# PDU_breakout.net
KiCad netlist of a schematic drawn in EAGLE
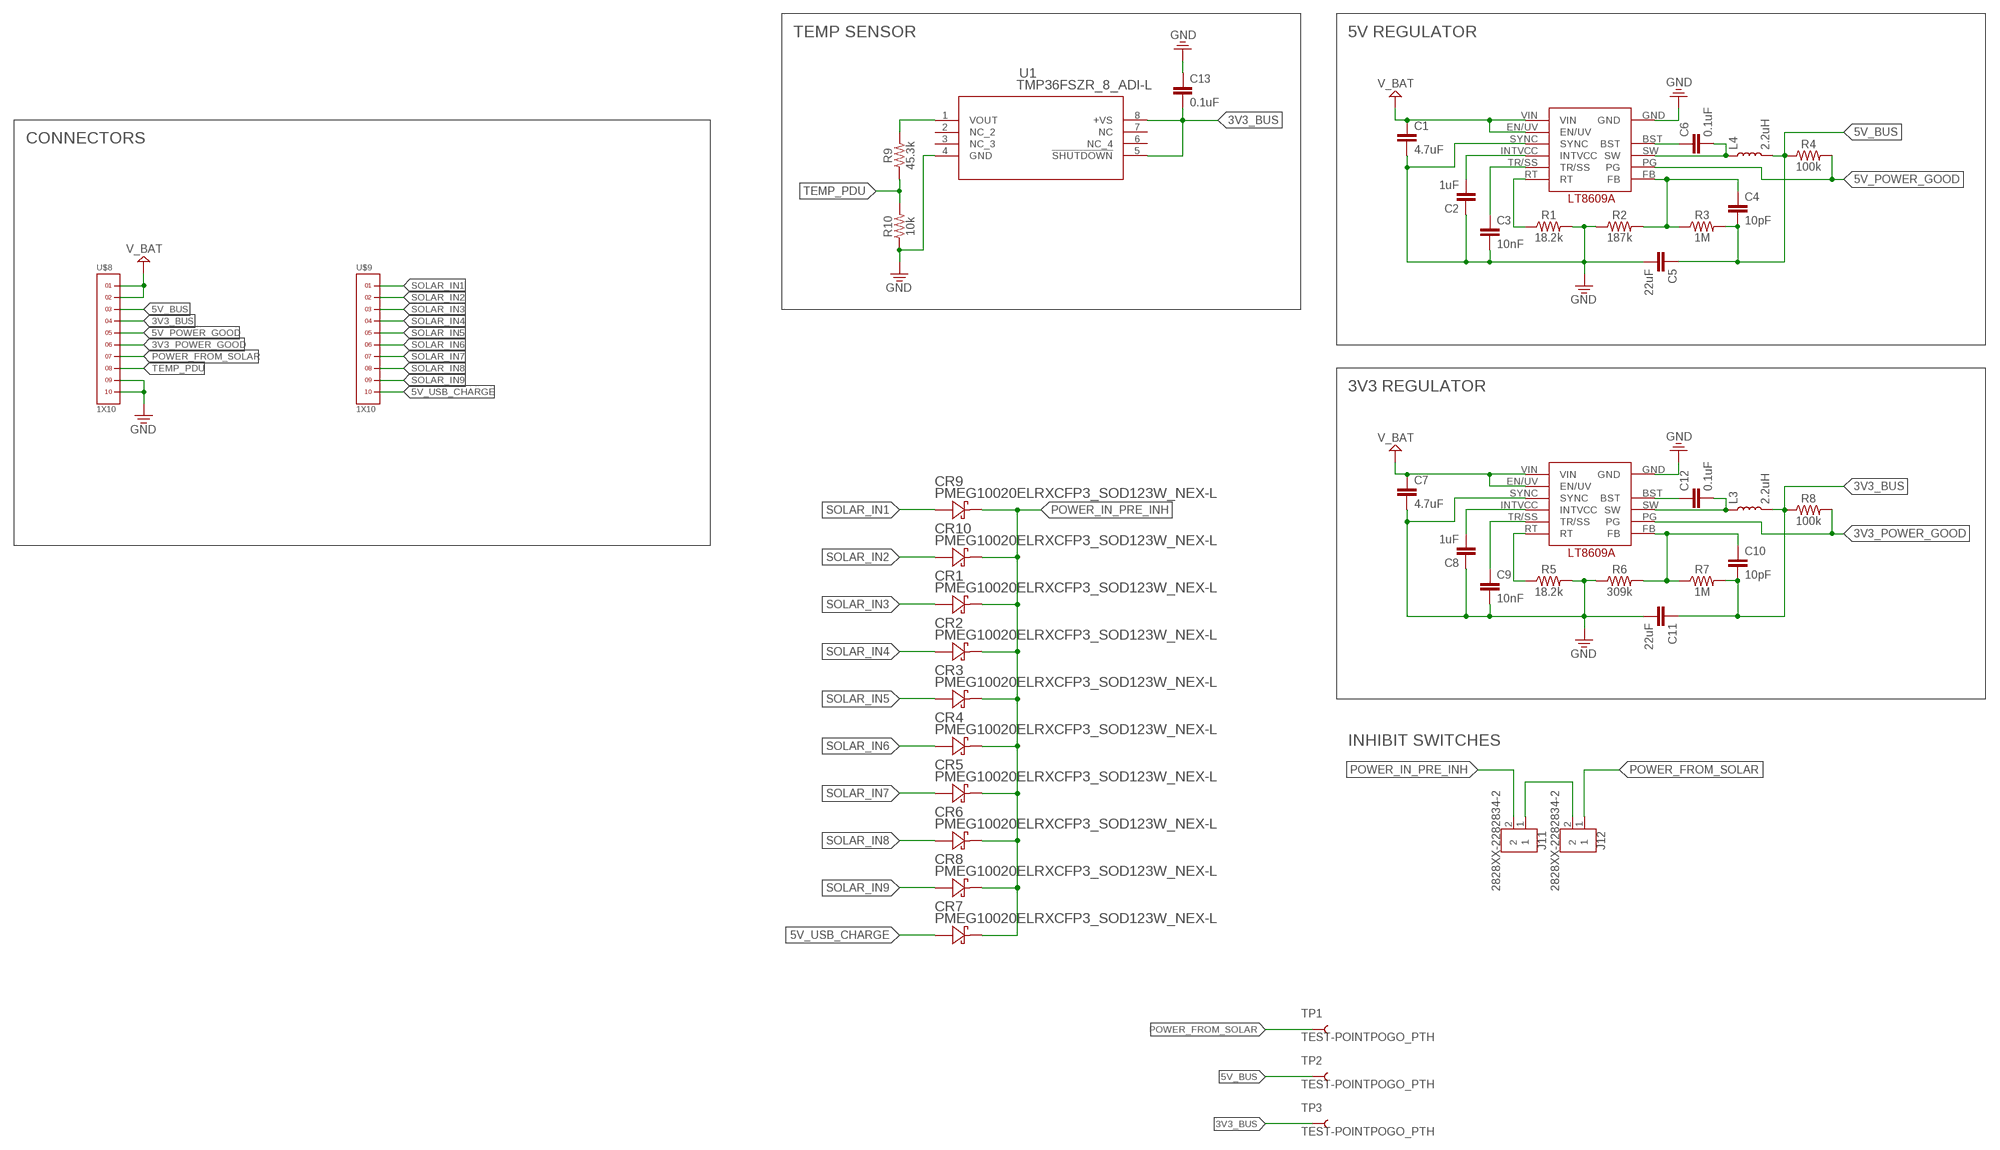
[diagram p0: schematic, sheet 1]

(export (version "E")
  (design (tool "Eeschema 10.0.6"))
  (components
    (comp (ref "C1")
      (value "4.7uF")
      (footprint "eagle-import:0805")
      (libsource (lib "eagle-import") (part "2.2UF-0805-25V-(+80/-20%)"))
    )
    (comp (ref "C2")
      (value "1uF")
      (footprint "eagle-import:0805")
      (libsource (lib "eagle-import") (part "2.2UF-0805-25V-(+80/-20%)"))
    )
    (comp (ref "C3")
      (value "10nF")
      (footprint "eagle-import:0805")
      (libsource (lib "eagle-import") (part "2.2UF-0805-25V-(+80/-20%)"))
    )
    (comp (ref "C4")
      (value "10pF")
      (footprint "eagle-import:0805")
      (libsource (lib "eagle-import") (part "2.2UF-0805-25V-(+80/-20%)"))
    )
    (comp (ref "C5")
      (value "22uF")
      (footprint "eagle-import:0805")
      (libsource (lib "eagle-import") (part "2.2UF-0805-25V-(+80/-20%)"))
    )
    (comp (ref "C6")
      (value "0.1uF")
      (footprint "eagle-import:0805")
      (libsource (lib "eagle-import") (part "2.2UF-0805-25V-(+80/-20%)"))
    )
    (comp (ref "C7")
      (value "4.7uF")
      (footprint "eagle-import:0805")
      (libsource (lib "eagle-import") (part "2.2UF-0805-25V-(+80/-20%)"))
    )
    (comp (ref "C8")
      (value "1uF")
      (footprint "eagle-import:0805")
      (libsource (lib "eagle-import") (part "2.2UF-0805-25V-(+80/-20%)"))
    )
    (comp (ref "C9")
      (value "10nF")
      (footprint "eagle-import:0805")
      (libsource (lib "eagle-import") (part "2.2UF-0805-25V-(+80/-20%)"))
    )
    (comp (ref "C10")
      (value "10pF")
      (footprint "eagle-import:0805")
      (libsource (lib "eagle-import") (part "2.2UF-0805-25V-(+80/-20%)"))
    )
    (comp (ref "C11")
      (value "22uF")
      (footprint "eagle-import:0805")
      (libsource (lib "eagle-import") (part "2.2UF-0805-25V-(+80/-20%)"))
    )
    (comp (ref "C12")
      (value "0.1uF")
      (footprint "eagle-import:0805")
      (libsource (lib "eagle-import") (part "2.2UF-0805-25V-(+80/-20%)"))
    )
    (comp (ref "C13")
      (value "0.1uF")
      (footprint "eagle-import:0805")
      (libsource (lib "eagle-import") (part "2.2UF-0805-25V-(+80/-20%)"))
    )
    (comp (ref "CR1")
      (value "PMEG10020ELRXCFP3_SOD123W_NEX-L")
      (footprint "eagle-import:CFP3_SOD123W_NEX-L")
      (fields
        (field (name "MANUFACTURER_PART_NUMBER") "PMEG10020ELRX")
        (field (name "COPYRIGHT") "Copyright (C) 2018 Accelerated Designs. All rights reserved")
      )
      (libsource (lib "eagle-import") (part "PMEG10020ELRXCFP3_SOD123W_NEX-L"))
    )
    (comp (ref "CR2")
      (value "PMEG10020ELRXCFP3_SOD123W_NEX-L")
      (footprint "eagle-import:CFP3_SOD123W_NEX-L")
      (fields
        (field (name "MANUFACTURER_PART_NUMBER") "PMEG10020ELRX")
        (field (name "COPYRIGHT") "Copyright (C) 2018 Accelerated Designs. All rights reserved")
      )
      (libsource (lib "eagle-import") (part "PMEG10020ELRXCFP3_SOD123W_NEX-L"))
    )
    (comp (ref "CR3")
      (value "PMEG10020ELRXCFP3_SOD123W_NEX-L")
      (footprint "eagle-import:CFP3_SOD123W_NEX-L")
      (fields
        (field (name "MANUFACTURER_PART_NUMBER") "PMEG10020ELRX")
        (field (name "COPYRIGHT") "Copyright (C) 2018 Accelerated Designs. All rights reserved")
      )
      (libsource (lib "eagle-import") (part "PMEG10020ELRXCFP3_SOD123W_NEX-L"))
    )
    (comp (ref "CR4")
      (value "PMEG10020ELRXCFP3_SOD123W_NEX-L")
      (footprint "eagle-import:CFP3_SOD123W_NEX-L")
      (fields
        (field (name "MANUFACTURER_PART_NUMBER") "PMEG10020ELRX")
        (field (name "COPYRIGHT") "Copyright (C) 2018 Accelerated Designs. All rights reserved")
      )
      (libsource (lib "eagle-import") (part "PMEG10020ELRXCFP3_SOD123W_NEX-L"))
    )
    (comp (ref "CR5")
      (value "PMEG10020ELRXCFP3_SOD123W_NEX-L")
      (footprint "eagle-import:CFP3_SOD123W_NEX-L")
      (fields
        (field (name "MANUFACTURER_PART_NUMBER") "PMEG10020ELRX")
        (field (name "COPYRIGHT") "Copyright (C) 2018 Accelerated Designs. All rights reserved")
      )
      (libsource (lib "eagle-import") (part "PMEG10020ELRXCFP3_SOD123W_NEX-L"))
    )
    (comp (ref "CR6")
      (value "PMEG10020ELRXCFP3_SOD123W_NEX-L")
      (footprint "eagle-import:CFP3_SOD123W_NEX-L")
      (fields
        (field (name "MANUFACTURER_PART_NUMBER") "PMEG10020ELRX")
        (field (name "COPYRIGHT") "Copyright (C) 2018 Accelerated Designs. All rights reserved")
      )
      (libsource (lib "eagle-import") (part "PMEG10020ELRXCFP3_SOD123W_NEX-L"))
    )
    (comp (ref "CR7")
      (value "PMEG10020ELRXCFP3_SOD123W_NEX-L")
      (footprint "eagle-import:CFP3_SOD123W_NEX-L")
      (fields
        (field (name "MANUFACTURER_PART_NUMBER") "PMEG10020ELRX")
        (field (name "COPYRIGHT") "Copyright (C) 2018 Accelerated Designs. All rights reserved")
      )
      (libsource (lib "eagle-import") (part "PMEG10020ELRXCFP3_SOD123W_NEX-L"))
    )
    (comp (ref "CR8")
      (value "PMEG10020ELRXCFP3_SOD123W_NEX-L")
      (footprint "eagle-import:CFP3_SOD123W_NEX-L")
      (fields
        (field (name "MANUFACTURER_PART_NUMBER") "PMEG10020ELRX")
        (field (name "COPYRIGHT") "Copyright (C) 2018 Accelerated Designs. All rights reserved")
      )
      (libsource (lib "eagle-import") (part "PMEG10020ELRXCFP3_SOD123W_NEX-L"))
    )
    (comp (ref "CR9")
      (value "PMEG10020ELRXCFP3_SOD123W_NEX-L")
      (footprint "eagle-import:CFP3_SOD123W_NEX-L")
      (fields
        (field (name "MANUFACTURER_PART_NUMBER") "PMEG10020ELRX")
        (field (name "COPYRIGHT") "Copyright (C) 2018 Accelerated Designs. All rights reserved")
      )
      (libsource (lib "eagle-import") (part "PMEG10020ELRXCFP3_SOD123W_NEX-L"))
    )
    (comp (ref "CR10")
      (value "PMEG10020ELRXCFP3_SOD123W_NEX-L")
      (footprint "eagle-import:CFP3_SOD123W_NEX-L")
      (fields
        (field (name "MANUFACTURER_PART_NUMBER") "PMEG10020ELRX")
        (field (name "COPYRIGHT") "Copyright (C) 2018 Accelerated Designs. All rights reserved")
      )
      (libsource (lib "eagle-import") (part "PMEG10020ELRXCFP3_SOD123W_NEX-L"))
    )
    (comp (ref "J11")
      (value "2828XX-2282834-2")
      (footprint "eagle-import:TERMBLK_254-2N")
      (fields (field (name "MANUFACTURER") "TE Connectivity AMP Connectors") (field (name "MPN") "282834-2 "))
      (libsource (lib "eagle-import") (part "2828XX-2282834-2"))
    )
    (comp (ref "J12")
      (value "2828XX-2282834-2")
      (footprint "eagle-import:TERMBLK_254-2N")
      (fields (field (name "MANUFACTURER") "TE Connectivity AMP Connectors") (field (name "MPN") "282834-2 "))
      (libsource (lib "eagle-import") (part "2828XX-2282834-2"))
    )
    (comp (ref "L3")
      (value "2.2uH")
      (footprint "eagle-import:XFL4020")
      (libsource (lib "eagle-import") (part "INDUCTOR-XFL40201.5UH"))
    )
    (comp (ref "L4")
      (value "2.2uH")
      (footprint "eagle-import:XFL4020")
      (libsource (lib "eagle-import") (part "INDUCTOR-XFL40201.5UH"))
    )
    (comp (ref "R1")
      (value "18.2k")
      (footprint "eagle-import:0805")
      (libsource (lib "eagle-import") (part "0.75OHM-0805-1/4W-1%"))
    )
    (comp (ref "R2")
      (value "187k")
      (footprint "eagle-import:0805")
      (libsource (lib "eagle-import") (part "0.75OHM-0805-1/4W-1%"))
    )
    (comp (ref "R3")
      (value "1M")
      (footprint "eagle-import:0805")
      (libsource (lib "eagle-import") (part "0.75OHM-0805-1/4W-1%"))
    )
    (comp (ref "R4")
      (value "100k")
      (footprint "eagle-import:0805")
      (libsource (lib "eagle-import") (part "0.75OHM-0805-1/4W-1%"))
    )
    (comp (ref "R5")
      (value "18.2k")
      (footprint "eagle-import:0805")
      (libsource (lib "eagle-import") (part "0.75OHM-0805-1/4W-1%"))
    )
    (comp (ref "R6")
      (value "309k")
      (footprint "eagle-import:0805")
      (libsource (lib "eagle-import") (part "0.75OHM-0805-1/4W-1%"))
    )
    (comp (ref "R7")
      (value "1M")
      (footprint "eagle-import:0805")
      (libsource (lib "eagle-import") (part "0.75OHM-0805-1/4W-1%"))
    )
    (comp (ref "R8")
      (value "100k")
      (footprint "eagle-import:0805")
      (libsource (lib "eagle-import") (part "0.75OHM-0805-1/4W-1%"))
    )
    (comp (ref "R9")
      (value "45.3k")
      (footprint "eagle-import:0805")
      (libsource (lib "eagle-import") (part "0.75OHM-0805-1/4W-1%"))
    )
    (comp (ref "R10")
      (value "10k")
      (footprint "eagle-import:0805")
      (libsource (lib "eagle-import") (part "0.75OHM-0805-1/4W-1%"))
    )
    (comp (ref "TP1")
      (value "TEST-POINTPOGO_PTH")
      (footprint "eagle-import:1X01_NO_SILK")
      (libsource (lib "eagle-import") (part "TEST-POINTPOGO_PTH"))
    )
    (comp (ref "TP2")
      (value "TEST-POINTPOGO_PTH")
      (footprint "eagle-import:1X01_NO_SILK")
      (libsource (lib "eagle-import") (part "TEST-POINTPOGO_PTH"))
    )
    (comp (ref "TP3")
      (value "TEST-POINTPOGO_PTH")
      (footprint "eagle-import:1X01_NO_SILK")
      (libsource (lib "eagle-import") (part "TEST-POINTPOGO_PTH"))
    )
    (comp (ref "U$1")
      (value "LT8609A-MSOP10")
      (footprint "eagle-import:LT8609A-MSE10")
      (libsource (lib "eagle-import") (part "LT8609A-MSOP10"))
    )
    (comp (ref "U$2")
      (value "LT8609A-MSOP10")
      (footprint "eagle-import:LT8609A-MSE10")
      (libsource (lib "eagle-import") (part "LT8609A-MSOP10"))
    )
    (comp (ref "U$8")
      (value "1X10")
      (footprint "eagle-import:1X10")
      (libsource (lib "eagle-import") (part "1X10"))
    )
    (comp (ref "U$9")
      (value "1X10")
      (footprint "eagle-import:1X10")
      (libsource (lib "eagle-import") (part "1X10"))
    )
    (comp (ref "U1")
      (value "TMP36FSZR_8_ADI-L")
      (footprint "eagle-import:R_8_ADI-L")
      (fields
        (field (name "MANUFACTURER_PART_NUMBER") "TMP36FSZ")
        (field (name "COPYRIGHT") "Copyright (C) 2021 Ultra Librarian. All rights reserved.")
      )
      (libsource (lib "eagle-import") (part "TMP36FSZR_8_ADI-L"))
    )
  )
  (nets
    (net (code "1") (name "3V3_BUS") (class "Default")
      (node (ref "C10") (pin "2") (pinfunction "2_2") (pintype "passive"))
      (node (ref "C11") (pin "1") (pinfunction "1_1") (pintype "passive"))
      (node (ref "C13") (pin "2") (pinfunction "2_2") (pintype "passive"))
      (node (ref "L3") (pin "P$2") (pinfunction "2_P$2") (pintype "passive"))
      (node (ref "R7") (pin "2") (pinfunction "2_2") (pintype "passive"))
      (node (ref "R8") (pin "1") (pinfunction "1_1") (pintype "passive"))
      (node (ref "TP3") (pin "1") (pinfunction "1_1") (pintype "bidirectional"))
      (node (ref "U$8") (pin "4") (pinfunction "4_4") (pintype "bidirectional"))
      (node (ref "U1") (pin "5") (pinfunction "~{SHUTDOWN}_5") (pintype "passive"))
      (node (ref "U1") (pin "8") (pinfunction "+VS_8") (pintype "power_in"))
    )
    (net (code "2") (name "3V3_POWER_GOOD") (class "Default")
      (node (ref "R8") (pin "2") (pinfunction "2_2") (pintype "passive"))
      (node (ref "U$2") (pin "PG") (pinfunction "PG_PG") (pintype "bidirectional"))
      (node (ref "U$8") (pin "6") (pinfunction "6_6") (pintype "bidirectional"))
    )
    (net (code "3") (name "5V_BUS") (class "Default")
      (node (ref "C4") (pin "2") (pinfunction "2_2") (pintype "passive"))
      (node (ref "C5") (pin "1") (pinfunction "1_1") (pintype "passive"))
      (node (ref "L4") (pin "P$2") (pinfunction "2_P$2") (pintype "passive"))
      (node (ref "R3") (pin "2") (pinfunction "2_2") (pintype "passive"))
      (node (ref "R4") (pin "1") (pinfunction "1_1") (pintype "passive"))
      (node (ref "TP2") (pin "1") (pinfunction "1_1") (pintype "bidirectional"))
      (node (ref "U$8") (pin "3") (pinfunction "3_3") (pintype "bidirectional"))
    )
    (net (code "4") (name "5V_POWER_GOOD") (class "Default")
      (node (ref "R4") (pin "2") (pinfunction "2_2") (pintype "passive"))
      (node (ref "U$1") (pin "PG") (pinfunction "PG_PG") (pintype "bidirectional"))
      (node (ref "U$8") (pin "5") (pinfunction "5_5") (pintype "bidirectional"))
    )
    (net (code "5") (name "5V_USB_CHARGE") (class "Default")
      (node (ref "CR7") (pin "2") (pinfunction "12_2") (pintype "passive"))
      (node (ref "U$9") (pin "10") (pinfunction "10_10") (pintype "bidirectional"))
    )
    (net (code "6") (name "GND") (class "Default")
      (node (ref "C1") (pin "2") (pinfunction "2_2") (pintype "passive"))
      (node (ref "C11") (pin "2") (pinfunction "2_2") (pintype "passive"))
      (node (ref "C13") (pin "1") (pinfunction "1_1") (pintype "passive"))
      (node (ref "C2") (pin "1") (pinfunction "1_1") (pintype "passive"))
      (node (ref "C3") (pin "2") (pinfunction "2_2") (pintype "passive"))
      (node (ref "C5") (pin "2") (pinfunction "2_2") (pintype "passive"))
      (node (ref "C7") (pin "2") (pinfunction "2_2") (pintype "passive"))
      (node (ref "C8") (pin "1") (pinfunction "1_1") (pintype "passive"))
      (node (ref "C9") (pin "2") (pinfunction "2_2") (pintype "passive"))
      (node (ref "R1") (pin "2") (pinfunction "2_2") (pintype "passive"))
      (node (ref "R10") (pin "1") (pinfunction "1_1") (pintype "passive"))
      (node (ref "R2") (pin "1") (pinfunction "1_1") (pintype "passive"))
      (node (ref "R5") (pin "2") (pinfunction "2_2") (pintype "passive"))
      (node (ref "R6") (pin "1") (pinfunction "1_1") (pintype "passive"))
      (node (ref "U$1") (pin "GND") (pinfunction "GND_GND") (pintype "bidirectional"))
      (node (ref "U$1") (pin "SYNC") (pinfunction "SYNC_SYNC") (pintype "bidirectional"))
      (node (ref "U$2") (pin "GND") (pinfunction "GND_GND") (pintype "bidirectional"))
      (node (ref "U$2") (pin "SYNC") (pinfunction "SYNC_SYNC") (pintype "bidirectional"))
      (node (ref "U$8") (pin "10") (pinfunction "10_10") (pintype "bidirectional"))
      (node (ref "U$8") (pin "9") (pinfunction "9_9") (pintype "bidirectional"))
      (node (ref "U1") (pin "4") (pinfunction "GND_4") (pintype "passive"))
    )
    (net (code "7") (name "Net-(C2-Pad2)") (class "Default")
      (node (ref "C2") (pin "2") (pinfunction "2_2") (pintype "passive"))
      (node (ref "U$1") (pin "INTVCC") (pinfunction "INTVCC_INTVCC") (pintype "bidirectional"))
    )
    (net (code "8") (name "Net-(C3-Pad1)") (class "Default")
      (node (ref "C3") (pin "1") (pinfunction "1_1") (pintype "passive"))
      (node (ref "U$1") (pin "TR/SS") (pinfunction "TR/SS_TR/SS") (pintype "bidirectional"))
    )
    (net (code "9") (name "Net-(C4-Pad1)") (class "Default")
      (node (ref "C4") (pin "1") (pinfunction "1_1") (pintype "passive"))
      (node (ref "R2") (pin "2") (pinfunction "2_2") (pintype "passive"))
      (node (ref "R3") (pin "1") (pinfunction "1_1") (pintype "passive"))
      (node (ref "U$1") (pin "FB") (pinfunction "FB_FB") (pintype "bidirectional"))
    )
    (net (code "10") (name "Net-(C6-Pad1)") (class "Default")
      (node (ref "C6") (pin "1") (pinfunction "1_1") (pintype "passive"))
      (node (ref "U$1") (pin "BST") (pinfunction "BST_BST") (pintype "bidirectional"))
    )
    (net (code "11") (name "Net-(C8-Pad2)") (class "Default")
      (node (ref "C8") (pin "2") (pinfunction "2_2") (pintype "passive"))
      (node (ref "U$2") (pin "INTVCC") (pinfunction "INTVCC_INTVCC") (pintype "bidirectional"))
    )
    (net (code "12") (name "Net-(C9-Pad1)") (class "Default")
      (node (ref "C9") (pin "1") (pinfunction "1_1") (pintype "passive"))
      (node (ref "U$2") (pin "TR/SS") (pinfunction "TR/SS_TR/SS") (pintype "bidirectional"))
    )
    (net (code "13") (name "Net-(C10-Pad1)") (class "Default")
      (node (ref "C10") (pin "1") (pinfunction "1_1") (pintype "passive"))
      (node (ref "R6") (pin "2") (pinfunction "2_2") (pintype "passive"))
      (node (ref "R7") (pin "1") (pinfunction "1_1") (pintype "passive"))
      (node (ref "U$2") (pin "FB") (pinfunction "FB_FB") (pintype "bidirectional"))
    )
    (net (code "14") (name "Net-(C12-Pad1)") (class "Default")
      (node (ref "C12") (pin "1") (pinfunction "1_1") (pintype "passive"))
      (node (ref "U$2") (pin "BST") (pinfunction "BST_BST") (pintype "bidirectional"))
    )
    (net (code "15") (name "Net-(J11-Pad1)") (class "Default")
      (node (ref "J11") (pin "1") (pinfunction "1_1") (pintype "bidirectional"))
      (node (ref "J12") (pin "2") (pinfunction "2_2") (pintype "bidirectional"))
    )
    (net (code "16") (name "Net-(L3-1)") (class "Default")
      (node (ref "C12") (pin "2") (pinfunction "2_2") (pintype "passive"))
      (node (ref "L3") (pin "P$1") (pinfunction "1_P$1") (pintype "passive"))
      (node (ref "U$2") (pin "SW") (pinfunction "SW_SW") (pintype "bidirectional"))
    )
    (net (code "17") (name "Net-(L4-1)") (class "Default")
      (node (ref "C6") (pin "2") (pinfunction "2_2") (pintype "passive"))
      (node (ref "L4") (pin "P$1") (pinfunction "1_P$1") (pintype "passive"))
      (node (ref "U$1") (pin "SW") (pinfunction "SW_SW") (pintype "bidirectional"))
    )
    (net (code "18") (name "Net-(R1-Pad1)") (class "Default")
      (node (ref "R1") (pin "1") (pinfunction "1_1") (pintype "passive"))
      (node (ref "U$1") (pin "RT") (pinfunction "RT_RT") (pintype "bidirectional"))
    )
    (net (code "19") (name "Net-(R5-Pad1)") (class "Default")
      (node (ref "R5") (pin "1") (pinfunction "1_1") (pintype "passive"))
      (node (ref "U$2") (pin "RT") (pinfunction "RT_RT") (pintype "bidirectional"))
    )
    (net (code "20") (name "Net-(U1-VOUT)") (class "Default")
      (node (ref "R9") (pin "2") (pinfunction "2_2") (pintype "passive"))
      (node (ref "U1") (pin "1") (pinfunction "VOUT_1") (pintype "output"))
    )
    (net (code "21") (name "POWER_FROM_SOLAR") (class "Default")
      (node (ref "J12") (pin "1") (pinfunction "1_1") (pintype "bidirectional"))
      (node (ref "TP1") (pin "1") (pinfunction "1_1") (pintype "bidirectional"))
      (node (ref "U$8") (pin "7") (pinfunction "7_7") (pintype "bidirectional"))
    )
    (net (code "22") (name "POWER_IN_PRE_INH") (class "Default")
      (node (ref "CR1") (pin "1") (pinfunction "11_1") (pintype "passive"))
      (node (ref "CR10") (pin "1") (pinfunction "11_1") (pintype "passive"))
      (node (ref "CR2") (pin "1") (pinfunction "11_1") (pintype "passive"))
      (node (ref "CR3") (pin "1") (pinfunction "11_1") (pintype "passive"))
      (node (ref "CR4") (pin "1") (pinfunction "11_1") (pintype "passive"))
      (node (ref "CR5") (pin "1") (pinfunction "11_1") (pintype "passive"))
      (node (ref "CR6") (pin "1") (pinfunction "11_1") (pintype "passive"))
      (node (ref "CR7") (pin "1") (pinfunction "11_1") (pintype "passive"))
      (node (ref "CR8") (pin "1") (pinfunction "11_1") (pintype "passive"))
      (node (ref "CR9") (pin "1") (pinfunction "11_1") (pintype "passive"))
      (node (ref "J11") (pin "2") (pinfunction "2_2") (pintype "bidirectional"))
    )
    (net (code "23") (name "SOLAR_IN1") (class "Default")
      (node (ref "CR9") (pin "2") (pinfunction "12_2") (pintype "passive"))
      (node (ref "U$9") (pin "1") (pinfunction "1_1") (pintype "bidirectional"))
    )
    (net (code "24") (name "SOLAR_IN2") (class "Default")
      (node (ref "CR10") (pin "2") (pinfunction "12_2") (pintype "passive"))
      (node (ref "U$9") (pin "2") (pinfunction "2_2") (pintype "bidirectional"))
    )
    (net (code "25") (name "SOLAR_IN3") (class "Default")
      (node (ref "CR1") (pin "2") (pinfunction "12_2") (pintype "passive"))
      (node (ref "U$9") (pin "3") (pinfunction "3_3") (pintype "bidirectional"))
    )
    (net (code "26") (name "SOLAR_IN4") (class "Default")
      (node (ref "CR2") (pin "2") (pinfunction "12_2") (pintype "passive"))
      (node (ref "U$9") (pin "4") (pinfunction "4_4") (pintype "bidirectional"))
    )
    (net (code "27") (name "SOLAR_IN5") (class "Default")
      (node (ref "CR3") (pin "2") (pinfunction "12_2") (pintype "passive"))
      (node (ref "U$9") (pin "5") (pinfunction "5_5") (pintype "bidirectional"))
    )
    (net (code "28") (name "SOLAR_IN6") (class "Default")
      (node (ref "CR4") (pin "2") (pinfunction "12_2") (pintype "passive"))
      (node (ref "U$9") (pin "6") (pinfunction "6_6") (pintype "bidirectional"))
    )
    (net (code "29") (name "SOLAR_IN7") (class "Default")
      (node (ref "CR5") (pin "2") (pinfunction "12_2") (pintype "passive"))
      (node (ref "U$9") (pin "7") (pinfunction "7_7") (pintype "bidirectional"))
    )
    (net (code "30") (name "SOLAR_IN8") (class "Default")
      (node (ref "CR6") (pin "2") (pinfunction "12_2") (pintype "passive"))
      (node (ref "U$9") (pin "8") (pinfunction "8_8") (pintype "bidirectional"))
    )
    (net (code "31") (name "SOLAR_IN9") (class "Default")
      (node (ref "CR8") (pin "2") (pinfunction "12_2") (pintype "passive"))
      (node (ref "U$9") (pin "9") (pinfunction "9_9") (pintype "bidirectional"))
    )
    (net (code "32") (name "TEMP_PDU") (class "Default")
      (node (ref "R10") (pin "2") (pinfunction "2_2") (pintype "passive"))
      (node (ref "R9") (pin "1") (pinfunction "1_1") (pintype "passive"))
      (node (ref "U$8") (pin "8") (pinfunction "8_8") (pintype "bidirectional"))
    )
    (net (code "33") (name "V_BAT") (class "Default")
      (node (ref "C1") (pin "1") (pinfunction "1_1") (pintype "passive"))
      (node (ref "C7") (pin "1") (pinfunction "1_1") (pintype "passive"))
      (node (ref "U$1") (pin "EN/UV") (pinfunction "EN/UV_EN/UV") (pintype "bidirectional"))
      (node (ref "U$1") (pin "VIN") (pinfunction "VIN_VIN") (pintype "bidirectional"))
      (node (ref "U$2") (pin "EN/UV") (pinfunction "EN/UV_EN/UV") (pintype "bidirectional"))
      (node (ref "U$2") (pin "VIN") (pinfunction "VIN_VIN") (pintype "bidirectional"))
      (node (ref "U$8") (pin "1") (pinfunction "1_1") (pintype "bidirectional"))
      (node (ref "U$8") (pin "2") (pinfunction "2_2") (pintype "bidirectional"))
    )
    (net (code "34") (name "unconnected-(U1-NC-Pad7)") (class "Default")
      (node (ref "U1") (pin "7") (pinfunction "NC_7") (pintype "no_connect"))
    )
    (net (code "35") (name "unconnected-(U1-NC_2-Pad2)") (class "Default")
      (node (ref "U1") (pin "2") (pinfunction "NC_2_2") (pintype "no_connect"))
    )
    (net (code "36") (name "unconnected-(U1-NC_3-Pad3)") (class "Default")
      (node (ref "U1") (pin "3") (pinfunction "NC_3_3") (pintype "no_connect"))
    )
    (net (code "37") (name "unconnected-(U1-NC_4-Pad6)") (class "Default")
      (node (ref "U1") (pin "6") (pinfunction "NC_4_6") (pintype "no_connect"))
    )
  )
)
